# cameralink.net
KiCad netlist of a schematic drawn in Altium Designer
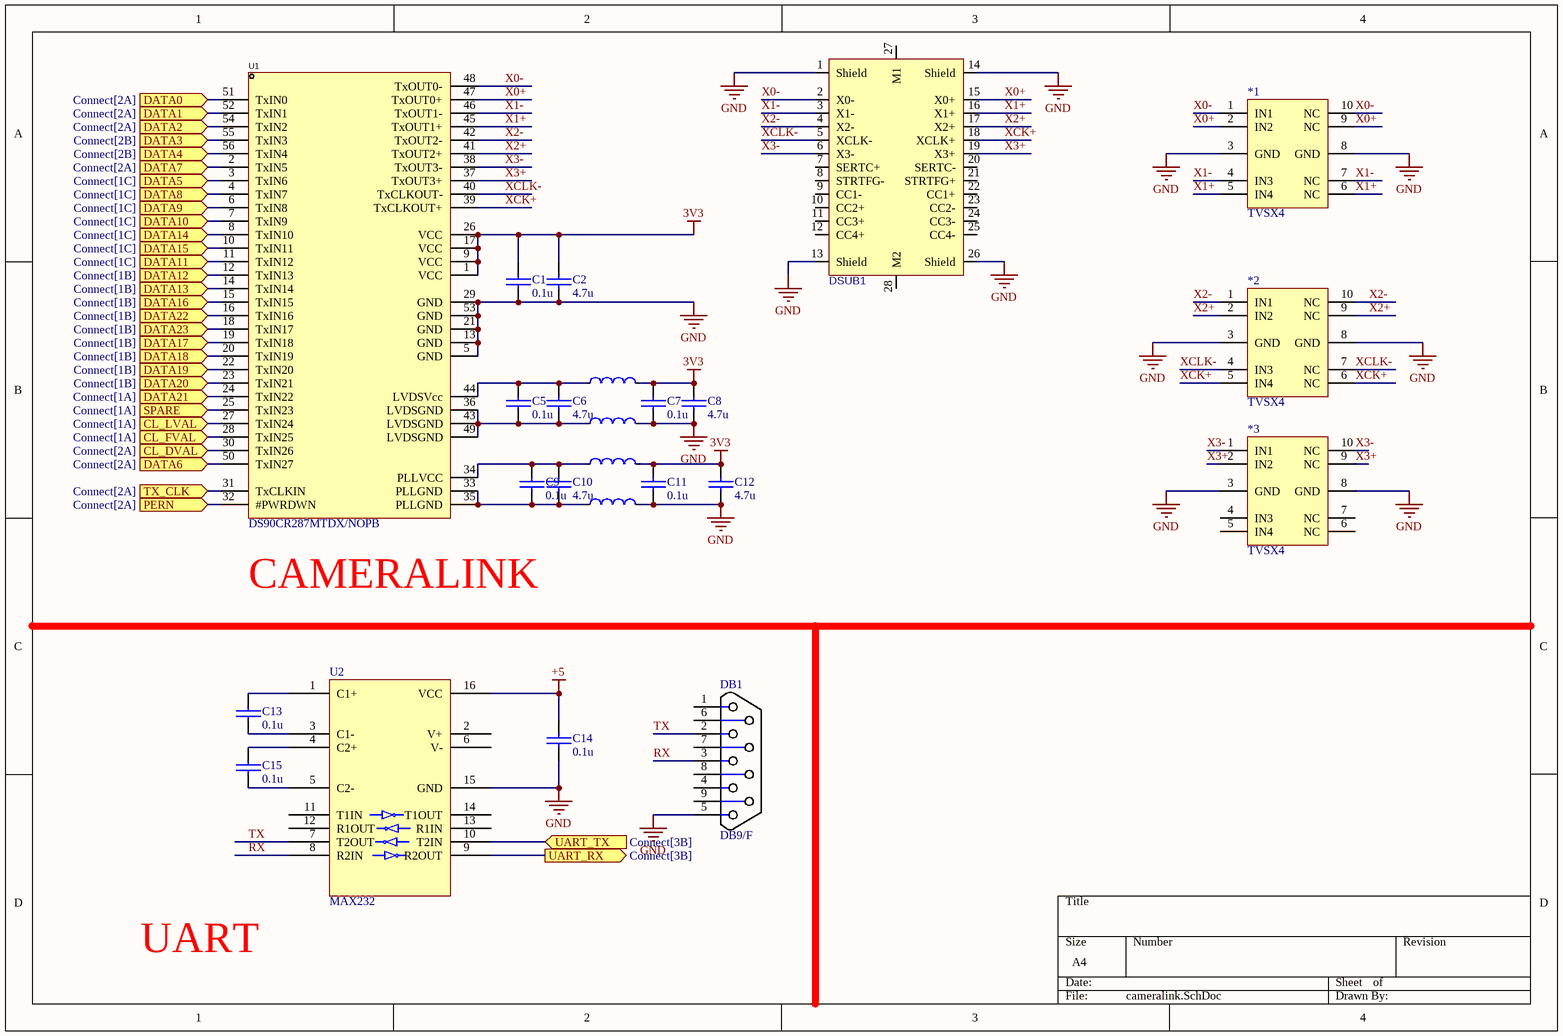
[diagram p0: cameralink.SchDoc]

(export (version "E")
  (design (tool "Eeschema 10.0.6"))
  (components
    (comp (ref "*1")
      (value "TVSX4")
      (footprint "DFN-10")
      (description "瞬态抑制二极管")
      (libsource (lib "0.05-mylib") (part "TVSX4"))
    )
    (comp (ref "*2")
      (value "TVSX4")
      (footprint "DFN-10")
      (description "瞬态抑制二极管")
      (libsource (lib "0.05-mylib") (part "TVSX4"))
    )
    (comp (ref "*3")
      (value "TVSX4")
      (footprint "DFN-10")
      (description "瞬态抑制二极管")
      (libsource (lib "0.05-mylib") (part "TVSX4"))
    )
    (comp (ref "C1")
      (value "0.1u")
      (footprint "0603C")
      (description "无极性电容")
      (libsource (lib "1.00-阻容感") (part "CAP"))
    )
    (comp (ref "C2")
      (value "4.7u")
      (footprint "0603C")
      (description "无极性电容")
      (libsource (lib "1.00-阻容感") (part "CAP"))
    )
    (comp (ref "C5")
      (value "0.1u")
      (footprint "0603C")
      (description "无极性电容")
      (libsource (lib "1.00-阻容感") (part "CAP"))
    )
    (comp (ref "C6")
      (value "4.7u")
      (footprint "0603C")
      (description "无极性电容")
      (libsource (lib "1.00-阻容感") (part "CAP"))
    )
    (comp (ref "C7")
      (value "0.1u")
      (footprint "0603C")
      (description "无极性电容")
      (libsource (lib "1.00-阻容感") (part "CAP"))
    )
    (comp (ref "C8")
      (value "4.7u")
      (footprint "0603C")
      (description "无极性电容")
      (libsource (lib "1.00-阻容感") (part "CAP"))
    )
    (comp (ref "C9")
      (value "0.1u")
      (footprint "0603C")
      (description "无极性电容")
      (libsource (lib "1.00-阻容感") (part "CAP"))
    )
    (comp (ref "C10")
      (value "4.7u")
      (footprint "0603C")
      (description "无极性电容")
      (libsource (lib "1.00-阻容感") (part "CAP"))
    )
    (comp (ref "C11")
      (value "0.1u")
      (footprint "0603C")
      (description "无极性电容")
      (libsource (lib "1.00-阻容感") (part "CAP"))
    )
    (comp (ref "C12")
      (value "4.7u")
      (footprint "0603C")
      (description "无极性电容")
      (libsource (lib "1.00-阻容感") (part "CAP"))
    )
    (comp (ref "C13")
      (value "0.1u")
      (footprint "0603C")
      (description "无极性电容")
      (libsource (lib "1.00-阻容感") (part "CAP"))
    )
    (comp (ref "C14")
      (value "0.1u")
      (footprint "0603C")
      (description "无极性电容")
      (libsource (lib "1.00-阻容感") (part "CAP"))
    )
    (comp (ref "C15")
      (value "0.1u")
      (footprint "0603C")
      (description "无极性电容")
      (libsource (lib "1.00-阻容感") (part "CAP"))
    )
    (comp (ref "DB1") (value "DB9/F") (footprint "DB9/F/90") (libsource (lib "8.04-串口") (part "DB9/F")))
    (comp (ref "DSUB1")
      (value "6321-026RDS1MWA02")
      (footprint "MDR-26-horizontal")
      (fields (field (name "BOM_SUPPLIER PART") "C843200") (field (name "CONTRIBUTOR") "LCSC"))
      (libsource (lib "0.04连接器") (part "MDR-26"))
    )
    (comp (ref "L3")
      (value "GZ1608D601TF")
      (footprint "0603L")
      (description "铁氧体磁珠")
      (fields (field (name "MANUFACTURER") "Sunlord(顺络)") (field (name "TOLERANCE") "±25%"))
      (libsource (lib "1.00-阻容感") (part "FB"))
    )
    (comp (ref "L4")
      (value "GZ1608D601TF")
      (footprint "0603L")
      (description "铁氧体磁珠")
      (fields (field (name "MANUFACTURER") "Sunlord(顺络)") (field (name "TOLERANCE") "±25%"))
      (libsource (lib "1.00-阻容感") (part "FB"))
    )
    (comp (ref "L5")
      (value "GZ1608D601TF")
      (footprint "0603L")
      (description "铁氧体磁珠")
      (fields (field (name "MANUFACTURER") "Sunlord(顺络)") (field (name "TOLERANCE") "±25%"))
      (libsource (lib "1.00-阻容感") (part "FB"))
    )
    (comp (ref "L6")
      (value "GZ1608D601TF")
      (footprint "0603L")
      (description "铁氧体磁珠")
      (fields (field (name "MANUFACTURER") "Sunlord(顺络)") (field (name "TOLERANCE") "±25%"))
      (libsource (lib "1.00-阻容感") (part "FB"))
    )
    (comp (ref "U1")
      (value "DS90CR287MTDX/NOPB")
      (footprint "TSSOP-56")
      (description "cameralink编码")
      (fields (field (name "MANUFACTURER") "TI(德州仪器)"))
      (libsource (lib "0.05-mylib") (part "DS90CR287MTDX/NOPB"))
    )
    (comp (ref "U2") (value "MAX232") (footprint "SOP16") (libsource (lib "7.06-通讯系列IC") (part "MAX232")))
  )
  (nets
    (net (code "1") (name "+5") (class "Default")
      (node (ref "C14") (pin "2") (pinfunction "2_2") (pintype "passive"))
      (node (ref "U2") (pin "16") (pinfunction "VCC_16") (pintype "passive"))
    )
    (net (code "2") (name "/CL_DVAL") (class "Default")
      (node (ref "U1") (pin "30") (pinfunction "TxIN26_30") (pintype "passive"))
    )
    (net (code "3") (name "/CL_FVAL") (class "Default")
      (node (ref "U1") (pin "28") (pinfunction "TxIN25_28") (pintype "passive"))
    )
    (net (code "4") (name "/CL_LVAL") (class "Default")
      (node (ref "U1") (pin "27") (pinfunction "TxIN24_27") (pintype "passive"))
    )
    (net (code "5") (name "/DATA0") (class "Default")
      (node (ref "U1") (pin "51") (pinfunction "TxIN0_51") (pintype "passive"))
    )
    (net (code "6") (name "/DATA1") (class "Default")
      (node (ref "U1") (pin "52") (pinfunction "TxIN1_52") (pintype "passive"))
    )
    (net (code "7") (name "/DATA2") (class "Default")
      (node (ref "U1") (pin "54") (pinfunction "TxIN2_54") (pintype "passive"))
    )
    (net (code "8") (name "/DATA3") (class "Default")
      (node (ref "U1") (pin "55") (pinfunction "TxIN3_55") (pintype "passive"))
    )
    (net (code "9") (name "/DATA4") (class "Default")
      (node (ref "U1") (pin "56") (pinfunction "TxIN4_56") (pintype "passive"))
    )
    (net (code "10") (name "/DATA5") (class "Default")
      (node (ref "U1") (pin "3") (pinfunction "TxIN6_3") (pintype "passive"))
    )
    (net (code "11") (name "/DATA6") (class "Default")
      (node (ref "U1") (pin "50") (pinfunction "TxIN27_50") (pintype "passive"))
    )
    (net (code "12") (name "/DATA7") (class "Default")
      (node (ref "U1") (pin "2") (pinfunction "TxIN5_2") (pintype "passive"))
    )
    (net (code "13") (name "/DATA8") (class "Default")
      (node (ref "U1") (pin "4") (pinfunction "TxIN7_4") (pintype "passive"))
    )
    (net (code "14") (name "/DATA9") (class "Default")
      (node (ref "U1") (pin "6") (pinfunction "TxIN8_6") (pintype "passive"))
    )
    (net (code "15") (name "/DATA10") (class "Default")
      (node (ref "U1") (pin "7") (pinfunction "TxIN9_7") (pintype "passive"))
    )
    (net (code "16") (name "/DATA11") (class "Default")
      (node (ref "U1") (pin "11") (pinfunction "TxIN12_11") (pintype "passive"))
    )
    (net (code "17") (name "/DATA12") (class "Default")
      (node (ref "U1") (pin "12") (pinfunction "TxIN13_12") (pintype "passive"))
    )
    (net (code "18") (name "/DATA13") (class "Default")
      (node (ref "U1") (pin "14") (pinfunction "TxIN14_14") (pintype "passive"))
    )
    (net (code "19") (name "/DATA14") (class "Default")
      (node (ref "U1") (pin "8") (pinfunction "TxIN10_8") (pintype "passive"))
    )
    (net (code "20") (name "/DATA15") (class "Default")
      (node (ref "U1") (pin "10") (pinfunction "TxIN11_10") (pintype "passive"))
    )
    (net (code "21") (name "/DATA16") (class "Default")
      (node (ref "U1") (pin "15") (pinfunction "TxIN15_15") (pintype "passive"))
    )
    (net (code "22") (name "/DATA17") (class "Default")
      (node (ref "U1") (pin "19") (pinfunction "TxIN18_19") (pintype "passive"))
    )
    (net (code "23") (name "/DATA18") (class "Default")
      (node (ref "U1") (pin "20") (pinfunction "TxIN19_20") (pintype "passive"))
    )
    (net (code "24") (name "/DATA19") (class "Default")
      (node (ref "U1") (pin "22") (pinfunction "TxIN20_22") (pintype "passive"))
    )
    (net (code "25") (name "/DATA20") (class "Default")
      (node (ref "U1") (pin "23") (pinfunction "TxIN21_23") (pintype "passive"))
    )
    (net (code "26") (name "/DATA21") (class "Default")
      (node (ref "U1") (pin "24") (pinfunction "TxIN22_24") (pintype "passive"))
    )
    (net (code "27") (name "/DATA22") (class "Default")
      (node (ref "U1") (pin "16") (pinfunction "TxIN16_16") (pintype "passive"))
    )
    (net (code "28") (name "/DATA23") (class "Default")
      (node (ref "U1") (pin "18") (pinfunction "TxIN17_18") (pintype "passive"))
    )
    (net (code "29") (name "/PERN") (class "Default")
      (node (ref "U1") (pin "32") (pinfunction "#PWRDWN_32") (pintype "passive"))
    )
    (net (code "30") (name "/RX") (class "Default")
      (node (ref "DB1") (pin "3") (pinfunction "3_3") (pintype "passive"))
      (node (ref "U2") (pin "8") (pinfunction "R2IN_8") (pintype "passive"))
    )
    (net (code "31") (name "/SPARE") (class "Default")
      (node (ref "U1") (pin "25") (pinfunction "TxIN23_25") (pintype "passive"))
    )
    (net (code "32") (name "/TX") (class "Default")
      (node (ref "DB1") (pin "2") (pinfunction "2_2") (pintype "passive"))
      (node (ref "U2") (pin "7") (pinfunction "T2OUT_7") (pintype "passive"))
    )
    (net (code "33") (name "/TX_CLK") (class "Default")
      (node (ref "U1") (pin "31") (pinfunction "TxCLKIN_31") (pintype "passive"))
    )
    (net (code "34") (name "/UART_RX") (class "Default")
      (node (ref "U2") (pin "9") (pinfunction "R2OUT_9") (pintype "passive"))
    )
    (net (code "35") (name "/UART_TX") (class "Default")
      (node (ref "U2") (pin "10") (pinfunction "T2IN_10") (pintype "passive"))
    )
    (net (code "36") (name "/X0+") (class "Default")
      (node (ref "*1") (pin "2") (pinfunction "IN2_2") (pintype "passive"))
      (node (ref "*1") (pin "9") (pinfunction "NC_9") (pintype "passive"))
      (node (ref "DSUB1") (pin "15") (pinfunction "X0+_15") (pintype "passive"))
      (node (ref "U1") (pin "47") (pinfunction "TxOUT0+_47") (pintype "passive"))
    )
    (net (code "37") (name "/X0-") (class "Default")
      (node (ref "*1") (pin "1") (pinfunction "IN1_1") (pintype "passive"))
      (node (ref "*1") (pin "10") (pinfunction "NC_10") (pintype "passive"))
      (node (ref "DSUB1") (pin "2") (pinfunction "X0-_2") (pintype "passive"))
      (node (ref "U1") (pin "48") (pinfunction "TxOUT0-_48") (pintype "passive"))
    )
    (net (code "38") (name "/X1+") (class "Default")
      (node (ref "*1") (pin "5") (pinfunction "IN4_5") (pintype "passive"))
      (node (ref "*1") (pin "6") (pinfunction "NC_6") (pintype "passive"))
      (node (ref "DSUB1") (pin "16") (pinfunction "X1+_16") (pintype "passive"))
      (node (ref "U1") (pin "45") (pinfunction "TxOUT1+_45") (pintype "passive"))
    )
    (net (code "39") (name "/X1-") (class "Default")
      (node (ref "*1") (pin "4") (pinfunction "IN3_4") (pintype "passive"))
      (node (ref "*1") (pin "7") (pinfunction "NC_7") (pintype "passive"))
      (node (ref "DSUB1") (pin "3") (pinfunction "X1-_3") (pintype "passive"))
      (node (ref "U1") (pin "46") (pinfunction "TxOUT1-_46") (pintype "passive"))
    )
    (net (code "40") (name "/X2+") (class "Default")
      (node (ref "*2") (pin "2") (pinfunction "IN2_2") (pintype "passive"))
      (node (ref "*2") (pin "9") (pinfunction "NC_9") (pintype "passive"))
      (node (ref "DSUB1") (pin "17") (pinfunction "X2+_17") (pintype "passive"))
      (node (ref "U1") (pin "41") (pinfunction "TxOUT2+_41") (pintype "passive"))
    )
    (net (code "41") (name "/X2-") (class "Default")
      (node (ref "*2") (pin "1") (pinfunction "IN1_1") (pintype "passive"))
      (node (ref "*2") (pin "10") (pinfunction "NC_10") (pintype "passive"))
      (node (ref "DSUB1") (pin "4") (pinfunction "X2-_4") (pintype "passive"))
      (node (ref "U1") (pin "42") (pinfunction "TxOUT2-_42") (pintype "passive"))
    )
    (net (code "42") (name "/X3+") (class "Default")
      (node (ref "*3") (pin "2") (pinfunction "IN2_2") (pintype "passive"))
      (node (ref "*3") (pin "9") (pinfunction "NC_9") (pintype "passive"))
      (node (ref "DSUB1") (pin "19") (pinfunction "X3+_19") (pintype "passive"))
      (node (ref "U1") (pin "37") (pinfunction "TxOUT3+_37") (pintype "passive"))
    )
    (net (code "43") (name "/X3-") (class "Default")
      (node (ref "*3") (pin "1") (pinfunction "IN1_1") (pintype "passive"))
      (node (ref "*3") (pin "10") (pinfunction "NC_10") (pintype "passive"))
      (node (ref "DSUB1") (pin "6") (pinfunction "X3-_6") (pintype "passive"))
      (node (ref "U1") (pin "38") (pinfunction "TxOUT3-_38") (pintype "passive"))
    )
    (net (code "44") (name "/XCK+") (class "Default")
      (node (ref "*2") (pin "5") (pinfunction "IN4_5") (pintype "passive"))
      (node (ref "*2") (pin "6") (pinfunction "NC_6") (pintype "passive"))
      (node (ref "DSUB1") (pin "18") (pinfunction "XCLK+_18") (pintype "passive"))
      (node (ref "U1") (pin "39") (pinfunction "TxCLKOUT+_39") (pintype "passive"))
    )
    (net (code "45") (name "/XCLK-") (class "Default")
      (node (ref "*2") (pin "4") (pinfunction "IN3_4") (pintype "passive"))
      (node (ref "*2") (pin "7") (pinfunction "NC_7") (pintype "passive"))
      (node (ref "DSUB1") (pin "5") (pinfunction "XCLK-_5") (pintype "passive"))
      (node (ref "U1") (pin "40") (pinfunction "TxCLKOUT-_40") (pintype "passive"))
    )
    (net (code "46") (name "3V3") (class "Default")
      (node (ref "C1") (pin "2") (pinfunction "2_2") (pintype "passive"))
      (node (ref "C11") (pin "2") (pinfunction "2_2") (pintype "passive"))
      (node (ref "C12") (pin "2") (pinfunction "2_2") (pintype "passive"))
      (node (ref "C2") (pin "2") (pinfunction "2_2") (pintype "passive"))
      (node (ref "C7") (pin "2") (pinfunction "2_2") (pintype "passive"))
      (node (ref "C8") (pin "2") (pinfunction "2_2") (pintype "passive"))
      (node (ref "L3") (pin "2") (pinfunction "2_2") (pintype "passive"))
      (node (ref "L5") (pin "2") (pinfunction "2_2") (pintype "passive"))
      (node (ref "U1") (pin "1") (pinfunction "VCC_1") (pintype "passive"))
      (node (ref "U1") (pin "17") (pinfunction "VCC_17") (pintype "passive"))
      (node (ref "U1") (pin "26") (pinfunction "VCC_26") (pintype "passive"))
      (node (ref "U1") (pin "9") (pinfunction "VCC_9") (pintype "passive"))
    )
    (net (code "47") (name "GND") (class "Default")
      (node (ref "*1") (pin "3") (pinfunction "GND_3") (pintype "passive"))
      (node (ref "*1") (pin "8") (pinfunction "GND_8") (pintype "passive"))
      (node (ref "*2") (pin "3") (pinfunction "GND_3") (pintype "passive"))
      (node (ref "*2") (pin "8") (pinfunction "GND_8") (pintype "passive"))
      (node (ref "*3") (pin "3") (pinfunction "GND_3") (pintype "passive"))
      (node (ref "*3") (pin "8") (pinfunction "GND_8") (pintype "passive"))
      (node (ref "C1") (pin "1") (pinfunction "1_1") (pintype "passive"))
      (node (ref "C11") (pin "1") (pinfunction "1_1") (pintype "passive"))
      (node (ref "C12") (pin "1") (pinfunction "1_1") (pintype "passive"))
      (node (ref "C14") (pin "1") (pinfunction "1_1") (pintype "passive"))
      (node (ref "C2") (pin "1") (pinfunction "1_1") (pintype "passive"))
      (node (ref "C7") (pin "1") (pinfunction "1_1") (pintype "passive"))
      (node (ref "C8") (pin "1") (pinfunction "1_1") (pintype "passive"))
      (node (ref "DB1") (pin "5") (pinfunction "5_5") (pintype "passive"))
      (node (ref "DSUB1") (pin "1") (pinfunction "Shield_1") (pintype "passive"))
      (node (ref "DSUB1") (pin "13") (pinfunction "Shield_13") (pintype "passive"))
      (node (ref "DSUB1") (pin "14") (pinfunction "Shield_14") (pintype "passive"))
      (node (ref "DSUB1") (pin "26") (pinfunction "Shield_26") (pintype "passive"))
      (node (ref "L4") (pin "2") (pinfunction "2_2") (pintype "passive"))
      (node (ref "L6") (pin "2") (pinfunction "2_2") (pintype "passive"))
      (node (ref "U1") (pin "13") (pinfunction "GND_13") (pintype "passive"))
      (node (ref "U1") (pin "21") (pinfunction "GND_21") (pintype "passive"))
      (node (ref "U1") (pin "29") (pinfunction "GND_29") (pintype "passive"))
      (node (ref "U1") (pin "5") (pinfunction "GND_5") (pintype "passive"))
      (node (ref "U1") (pin "53") (pinfunction "GND_53") (pintype "passive"))
      (node (ref "U2") (pin "15") (pinfunction "GND_15") (pintype "passive"))
    )
    (net (code "48") (name "Net-(C5-Pad1)") (class "Default")
      (node (ref "C5") (pin "1") (pinfunction "1_1") (pintype "passive"))
      (node (ref "C6") (pin "1") (pinfunction "1_1") (pintype "passive"))
      (node (ref "L4") (pin "1") (pinfunction "1_1") (pintype "passive"))
      (node (ref "U1") (pin "36") (pinfunction "LVDSGND_36") (pintype "passive"))
      (node (ref "U1") (pin "43") (pinfunction "LVDSGND_43") (pintype "passive"))
      (node (ref "U1") (pin "49") (pinfunction "LVDSGND_49") (pintype "passive"))
    )
    (net (code "49") (name "Net-(C10-Pad1)") (class "Default")
      (node (ref "C10") (pin "1") (pinfunction "1_1") (pintype "passive"))
      (node (ref "C9") (pin "1") (pinfunction "1_1") (pintype "passive"))
      (node (ref "L6") (pin "1") (pinfunction "1_1") (pintype "passive"))
      (node (ref "U1") (pin "33") (pinfunction "PLLGND_33") (pintype "passive"))
      (node (ref "U1") (pin "35") (pinfunction "PLLGND_35") (pintype "passive"))
    )
    (net (code "50") (name "Net-(U1-LVDSVcc)") (class "Default")
      (node (ref "C5") (pin "2") (pinfunction "2_2") (pintype "passive"))
      (node (ref "C6") (pin "2") (pinfunction "2_2") (pintype "passive"))
      (node (ref "L3") (pin "1") (pinfunction "1_1") (pintype "passive"))
      (node (ref "U1") (pin "44") (pinfunction "LVDSVcc_44") (pintype "passive"))
    )
    (net (code "51") (name "Net-(U1-PLLVCC)") (class "Default")
      (node (ref "C10") (pin "2") (pinfunction "2_2") (pintype "passive"))
      (node (ref "C9") (pin "2") (pinfunction "2_2") (pintype "passive"))
      (node (ref "L5") (pin "1") (pinfunction "1_1") (pintype "passive"))
      (node (ref "U1") (pin "34") (pinfunction "PLLVCC_34") (pintype "passive"))
    )
    (net (code "52") (name "Net-(U2-C1+)") (class "Default")
      (node (ref "C13") (pin "2") (pinfunction "2_2") (pintype "passive"))
      (node (ref "U2") (pin "1") (pinfunction "C1+_1") (pintype "passive"))
    )
    (net (code "53") (name "Net-(U2-C1-)") (class "Default")
      (node (ref "C13") (pin "1") (pinfunction "1_1") (pintype "passive"))
      (node (ref "U2") (pin "3") (pinfunction "C1-_3") (pintype "passive"))
    )
    (net (code "54") (name "Net-(U2-C2+)") (class "Default")
      (node (ref "C15") (pin "2") (pinfunction "2_2") (pintype "passive"))
      (node (ref "U2") (pin "4") (pinfunction "C2+_4") (pintype "passive"))
    )
    (net (code "55") (name "Net-(U2-C2-)") (class "Default")
      (node (ref "C15") (pin "1") (pinfunction "1_1") (pintype "passive"))
      (node (ref "U2") (pin "5") (pinfunction "C2-_5") (pintype "passive"))
    )
    (net (code "56") (name "unconnected-(*3-IN3-Pad4)") (class "Default")
      (node (ref "*3") (pin "4") (pinfunction "IN3_4") (pintype "passive"))
    )
    (net (code "57") (name "unconnected-(*3-IN4-Pad5)") (class "Default")
      (node (ref "*3") (pin "5") (pinfunction "IN4_5") (pintype "passive"))
    )
    (net (code "58") (name "unconnected-(*3-NC-Pad6)") (class "Default")
      (node (ref "*3") (pin "6") (pinfunction "NC_6") (pintype "passive"))
    )
    (net (code "59") (name "unconnected-(*3-NC-Pad7)") (class "Default")
      (node (ref "*3") (pin "7") (pinfunction "NC_7") (pintype "passive"))
    )
    (net (code "60") (name "unconnected-(DB1-Pad1)") (class "Default")
      (node (ref "DB1") (pin "1") (pinfunction "1_1") (pintype "passive"))
    )
    (net (code "61") (name "unconnected-(DB1-Pad4)") (class "Default")
      (node (ref "DB1") (pin "4") (pinfunction "4_4") (pintype "passive"))
    )
    (net (code "62") (name "unconnected-(DB1-Pad6)") (class "Default")
      (node (ref "DB1") (pin "6") (pinfunction "6_6") (pintype "passive"))
    )
    (net (code "63") (name "unconnected-(DB1-Pad7)") (class "Default")
      (node (ref "DB1") (pin "7") (pinfunction "7_7") (pintype "passive"))
    )
    (net (code "64") (name "unconnected-(DB1-Pad8)") (class "Default")
      (node (ref "DB1") (pin "8") (pinfunction "8_8") (pintype "passive"))
    )
    (net (code "65") (name "unconnected-(DB1-Pad9)") (class "Default")
      (node (ref "DB1") (pin "9") (pinfunction "9_9") (pintype "passive"))
    )
    (net (code "66") (name "unconnected-(DSUB1-CC1+-Pad22)") (class "Default")
      (node (ref "DSUB1") (pin "22") (pinfunction "CC1+_22") (pintype "passive"))
    )
    (net (code "67") (name "unconnected-(DSUB1-CC1--Pad9)") (class "Default")
      (node (ref "DSUB1") (pin "9") (pinfunction "CC1-_9") (pintype "passive"))
    )
    (net (code "68") (name "unconnected-(DSUB1-CC2+-Pad10)") (class "Default")
      (node (ref "DSUB1") (pin "10") (pinfunction "CC2+_10") (pintype "passive"))
    )
    (net (code "69") (name "unconnected-(DSUB1-CC2--Pad23)") (class "Default")
      (node (ref "DSUB1") (pin "23") (pinfunction "CC2-_23") (pintype "passive"))
    )
    (net (code "70") (name "unconnected-(DSUB1-CC3+-Pad11)") (class "Default")
      (node (ref "DSUB1") (pin "11") (pinfunction "CC3+_11") (pintype "passive"))
    )
    (net (code "71") (name "unconnected-(DSUB1-CC3--Pad24)") (class "Default")
      (node (ref "DSUB1") (pin "24") (pinfunction "CC3-_24") (pintype "passive"))
    )
    (net (code "72") (name "unconnected-(DSUB1-CC4+-Pad12)") (class "Default")
      (node (ref "DSUB1") (pin "12") (pinfunction "CC4+_12") (pintype "passive"))
    )
    (net (code "73") (name "unconnected-(DSUB1-CC4--Pad25)") (class "Default")
      (node (ref "DSUB1") (pin "25") (pinfunction "CC4-_25") (pintype "passive"))
    )
    (net (code "74") (name "unconnected-(DSUB1-M1-Pad27)") (class "Default")
      (node (ref "DSUB1") (pin "27") (pinfunction "M1_27") (pintype "passive"))
    )
    (net (code "75") (name "unconnected-(DSUB1-M2-Pad28)") (class "Default")
      (node (ref "DSUB1") (pin "28") (pinfunction "M2_28") (pintype "passive"))
    )
    (net (code "76") (name "unconnected-(DSUB1-SERTC+-Pad7)") (class "Default")
      (node (ref "DSUB1") (pin "7") (pinfunction "SERTC+_7") (pintype "passive"))
    )
    (net (code "77") (name "unconnected-(DSUB1-SERTC--Pad20)") (class "Default")
      (node (ref "DSUB1") (pin "20") (pinfunction "SERTC-_20") (pintype "passive"))
    )
    (net (code "78") (name "unconnected-(DSUB1-STRTFG+-Pad21)") (class "Default")
      (node (ref "DSUB1") (pin "21") (pinfunction "STRTFG+_21") (pintype "passive"))
    )
    (net (code "79") (name "unconnected-(DSUB1-STRTFG--Pad8)") (class "Default")
      (node (ref "DSUB1") (pin "8") (pinfunction "STRTFG-_8") (pintype "passive"))
    )
    (net (code "80") (name "unconnected-(U2-R1IN-Pad13)") (class "Default")
      (node (ref "U2") (pin "13") (pinfunction "R1IN_13") (pintype "passive"))
    )
    (net (code "81") (name "unconnected-(U2-R1OUT-Pad12)") (class "Default")
      (node (ref "U2") (pin "12") (pinfunction "R1OUT_12") (pintype "passive"))
    )
    (net (code "82") (name "unconnected-(U2-T1IN-Pad11)") (class "Default")
      (node (ref "U2") (pin "11") (pinfunction "T1IN_11") (pintype "passive"))
    )
    (net (code "83") (name "unconnected-(U2-T1OUT-Pad14)") (class "Default")
      (node (ref "U2") (pin "14") (pinfunction "T1OUT_14") (pintype "passive"))
    )
    (net (code "84") (name "unconnected-(U2-V+-Pad2)") (class "Default")
      (node (ref "U2") (pin "2") (pinfunction "V+_2") (pintype "passive"))
    )
    (net (code "85") (name "unconnected-(U2-V--Pad6)") (class "Default")
      (node (ref "U2") (pin "6") (pinfunction "V-_6") (pintype "passive"))
    )
  )
)
